# onion_dock.net
KiCad netlist of a schematic drawn in Altium Designer
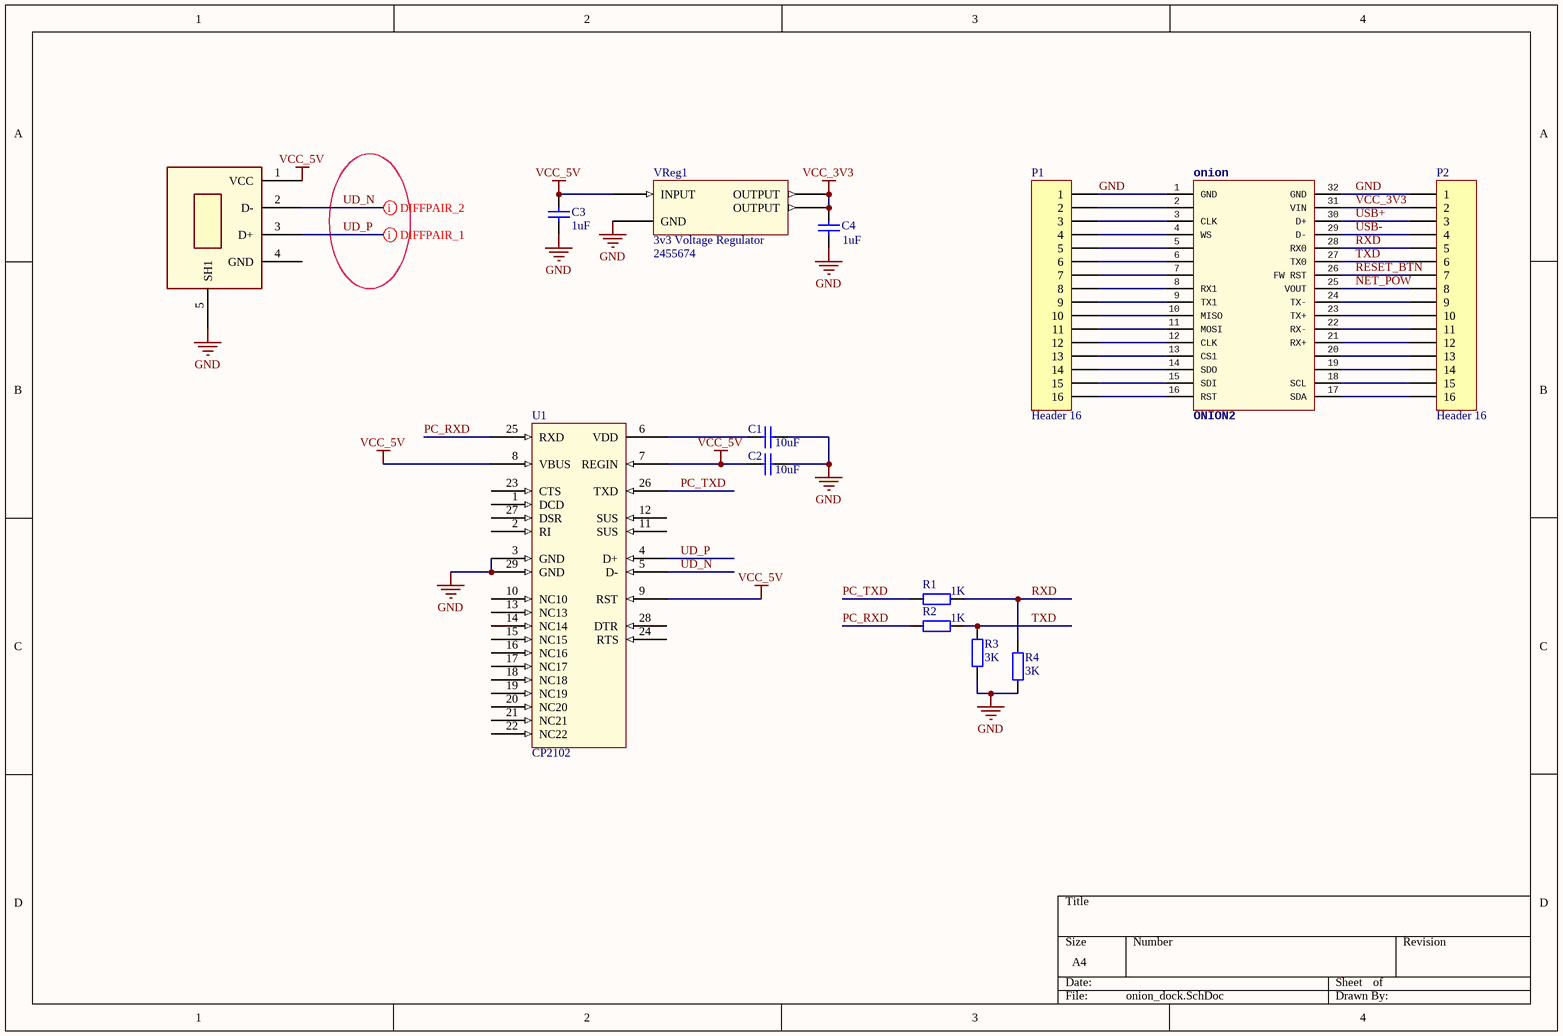
[diagram p0: onion_dock.SchDoc]

(export (version "E")
  (design (tool "Eeschema 10.0.6"))
  (components
    (comp (ref "C1")
      (value "10uF")
      (footprint "C0805")
      (description "SMD Multilayer Ceramic Capacitor, 10 µF, ± 10%, X5R, 25 V, 0805 [2012 Metric]")
      (fields (field (name "Comment") "C0805_10uF_25V"))
      (libsource (lib "Capacitors") (part "C0805_10uF_25V"))
    )
    (comp (ref "C2")
      (value "10uF")
      (footprint "C0805")
      (description "SMD Multilayer Ceramic Capacitor, 10 µF, ± 10%, X5R, 25 V, 0805 [2012 Metric]")
      (fields (field (name "Comment") "C0805_10uF_25V"))
      (libsource (lib "Capacitors") (part "C0805_10uF_25V"))
    )
    (comp (ref "C3")
      (value "1uF")
      (footprint "C0805")
      (description "SMD Multilayer Ceramic Capacitor, 1 µF, ± 10%, X7R, 25 V, 0805 [2012 Metric]")
      (fields (field (name "Comment") "C0805_1uF_25V"))
      (libsource (lib "Capacitors") (part "C0805_1uF_25V"))
    )
    (comp (ref "C4")
      (value "1uF")
      (footprint "C0805")
      (description "SMD Multilayer Ceramic Capacitor, 1 µF, ± 10%, X7R, 25 V, 0805 [2012 Metric]")
      (fields (field (name "Comment") "C0805_1uF_25V"))
      (libsource (lib "Capacitors") (part "C0805_1uF_25V"))
    )
    (comp (ref "onion") (value "ONION2") (footprint "ONION2") (libsource (lib "ICs") (part "ONION2")))
    (comp (ref "P1")
      (value "Header 16")
      (footprint "HDR1X16")
      (description "Header, 16-Pin")
      (fields (field (name "PUBLISHER") "Altium Limited"))
      (libsource (lib "Connectors") (part "Header 16"))
    )
    (comp (ref "P2")
      (value "Header 16")
      (footprint "HDR1X16")
      (description "Header, 16-Pin")
      (fields (field (name "PUBLISHER") "Altium Limited"))
      (libsource (lib "") (part "Header 16_1"))
    )
    (comp (ref "R1")
      (value "1K")
      (footprint "R0805")
      (description "RES, THICK FILM, 1K, 1%,100mW, 0805")
      (fields (field (name "POWER") "0.1W") (field (name "Comment") "R0805_1K_100mW"))
      (libsource (lib "Resistors") (part "R0805_1K_100mW"))
    )
    (comp (ref "R2")
      (value "1K")
      (footprint "R0805")
      (description "RES, THICK FILM, 1K, 1%,100mW, 0805")
      (fields (field (name "POWER") "0.1W") (field (name "Comment") "R0805_1K_100mW"))
      (libsource (lib "Resistors") (part "R0805_1K_100mW"))
    )
    (comp (ref "R3")
      (value "3K")
      (footprint "R0805")
      (description "RES, THICK FILM, 1K, 1%,100mW, 0805")
      (fields (field (name "Comment") "R0805_1K_100mW"))
      (libsource (lib "Resistors") (part "R0805_1K_100mW"))
    )
    (comp (ref "R4")
      (value "3K")
      (footprint "R0805")
      (description "RES, THICK FILM, 1K, 1%,100mW, 0805")
      (fields (field (name "Comment") "R0805_1K_100mW"))
      (libsource (lib "Resistors") (part "R0805_1K_100mW"))
    )
    (comp (ref "U1")
      (value "CP2102")
      (footprint "QFN50P500X500X100_HS-29N")
      (libsource (lib "ICs") (part "CP2102"))
    )
    (comp (ref "USB") (value "USB") (footprint "MicroUSB") (libsource (lib "Connectors") (part "USB")))
    (comp (ref "VReg1")
      (value "3v3 Voltage Regulator")
      (footprint "SOT230P700X180-4N")
      (fields (field (name "SUPPLIER PART NUMBER 1") "2455674"))
      (libsource (lib "ICs") (part "1117LV33"))
    )
  )
  (nets
    (net (code "1") (name "/NET_POW") (class "Default")
      (node (ref "P2") (pin "8") (pinfunction "8_8") (pintype "passive"))
      (node (ref "onion") (pin "25") (pinfunction "VOUT_25") (pintype "passive"))
    )
    (net (code "2") (name "/PC_RXD") (class "Default")
      (node (ref "R2") (pin "1") (pinfunction "1_1") (pintype "passive"))
      (node (ref "U1") (pin "25") (pinfunction "RXD_25") (pintype "input"))
    )
    (net (code "3") (name "/PC_TXD") (class "Default")
      (node (ref "R1") (pin "1") (pinfunction "1_1") (pintype "passive"))
      (node (ref "U1") (pin "26") (pinfunction "TXD_26") (pintype "input"))
    )
    (net (code "4") (name "/RESET_BTN") (class "Default")
      (node (ref "P2") (pin "7") (pinfunction "7_7") (pintype "passive"))
      (node (ref "onion") (pin "26") (pinfunction "FW_RST_26") (pintype "passive"))
    )
    (net (code "5") (name "/RXD") (class "Default")
      (node (ref "P2") (pin "5") (pinfunction "5_5") (pintype "passive"))
      (node (ref "R1") (pin "2") (pinfunction "2_2") (pintype "passive"))
      (node (ref "R4") (pin "2") (pinfunction "2_2") (pintype "passive"))
      (node (ref "onion") (pin "28") (pinfunction "RX0_28") (pintype "passive"))
    )
    (net (code "6") (name "/TXD") (class "Default")
      (node (ref "P2") (pin "6") (pinfunction "6_6") (pintype "passive"))
      (node (ref "R2") (pin "2") (pinfunction "2_2") (pintype "passive"))
      (node (ref "R3") (pin "2") (pinfunction "2_2") (pintype "passive"))
      (node (ref "onion") (pin "27") (pinfunction "TX0_27") (pintype "passive"))
    )
    (net (code "7") (name "/UD_N") (class "Default")
      (node (ref "U1") (pin "5") (pinfunction "D-_5") (pintype "input"))
      (node (ref "USB") (pin "2") (pinfunction "D-_2") (pintype "passive"))
    )
    (net (code "8") (name "/UD_P") (class "Default")
      (node (ref "U1") (pin "4") (pinfunction "D+_4") (pintype "input"))
      (node (ref "USB") (pin "3") (pinfunction "D+_3") (pintype "passive"))
    )
    (net (code "9") (name "/USB+") (class "Default")
      (node (ref "P2") (pin "3") (pinfunction "3_3") (pintype "passive"))
      (node (ref "onion") (pin "30") (pinfunction "D+_30") (pintype "passive"))
    )
    (net (code "10") (name "/USB-") (class "Default")
      (node (ref "P2") (pin "4") (pinfunction "4_4") (pintype "passive"))
      (node (ref "onion") (pin "29") (pinfunction "D-_29") (pintype "passive"))
    )
    (net (code "11") (name "GND") (class "Default")
      (node (ref "C1") (pin "2") (pinfunction "2_2") (pintype "passive"))
      (node (ref "C2") (pin "2") (pinfunction "2_2") (pintype "passive"))
      (node (ref "C3") (pin "1") (pinfunction "1_1") (pintype "passive"))
      (node (ref "C4") (pin "1") (pinfunction "1_1") (pintype "passive"))
      (node (ref "P1") (pin "1") (pinfunction "1_1") (pintype "passive"))
      (node (ref "P2") (pin "1") (pinfunction "1_1") (pintype "passive"))
      (node (ref "R3") (pin "1") (pinfunction "1_1") (pintype "passive"))
      (node (ref "R4") (pin "1") (pinfunction "1_1") (pintype "passive"))
      (node (ref "U1") (pin "29") (pinfunction "GND_29") (pintype "input"))
      (node (ref "U1") (pin "3") (pinfunction "GND_3") (pintype "input"))
      (node (ref "USB") (pin "5") (pinfunction "SH1_5") (pintype "passive"))
      (node (ref "VReg1") (pin "1") (pinfunction "GND_1") (pintype "power_in"))
      (node (ref "onion") (pin "1") (pinfunction "GND_1") (pintype "passive"))
      (node (ref "onion") (pin "32") (pinfunction "GND_32") (pintype "passive"))
    )
    (net (code "12") (name "Net-(P1-Pad2)") (class "Default")
      (node (ref "P1") (pin "2") (pinfunction "2_2") (pintype "passive"))
      (node (ref "onion") (pin "2") (pintype "passive"))
    )
    (net (code "13") (name "Net-(P1-Pad3)") (class "Default")
      (node (ref "P1") (pin "3") (pinfunction "3_3") (pintype "passive"))
      (node (ref "onion") (pin "3") (pinfunction "CLK_3") (pintype "passive"))
    )
    (net (code "14") (name "Net-(P1-Pad5)") (class "Default")
      (node (ref "P1") (pin "5") (pinfunction "5_5") (pintype "passive"))
      (node (ref "onion") (pin "5") (pintype "passive"))
    )
    (net (code "15") (name "Net-(P1-Pad6)") (class "Default")
      (node (ref "P1") (pin "6") (pinfunction "6_6") (pintype "passive"))
      (node (ref "onion") (pin "6") (pintype "passive"))
    )
    (net (code "16") (name "Net-(P1-Pad7)") (class "Default")
      (node (ref "P1") (pin "7") (pinfunction "7_7") (pintype "passive"))
      (node (ref "onion") (pin "7") (pintype "passive"))
    )
    (net (code "17") (name "Net-(P1-Pad12)") (class "Default")
      (node (ref "P1") (pin "12") (pinfunction "12_12") (pintype "passive"))
      (node (ref "onion") (pin "12") (pinfunction "CLK_12") (pintype "passive"))
    )
    (net (code "18") (name "Net-(P2-Pad13)") (class "Default")
      (node (ref "P2") (pin "13") (pinfunction "13_13") (pintype "passive"))
      (node (ref "onion") (pin "20") (pintype "passive"))
    )
    (net (code "19") (name "Net-(P2-Pad14)") (class "Default")
      (node (ref "P2") (pin "14") (pinfunction "14_14") (pintype "passive"))
      (node (ref "onion") (pin "19") (pintype "passive"))
    )
    (net (code "20") (name "Net-(U1-VDD)") (class "Default")
      (node (ref "C1") (pin "1") (pinfunction "1_1") (pintype "passive"))
      (node (ref "U1") (pin "6") (pinfunction "VDD_6") (pintype "open_collector"))
    )
    (net (code "21") (name "Net-(onion-CS1)") (class "Default")
      (node (ref "P1") (pin "13") (pinfunction "13_13") (pintype "passive"))
      (node (ref "onion") (pin "13") (pinfunction "CS1_13") (pintype "passive"))
    )
    (net (code "22") (name "Net-(onion-MISO)") (class "Default")
      (node (ref "P1") (pin "10") (pinfunction "10_10") (pintype "passive"))
      (node (ref "onion") (pin "10") (pinfunction "MISO_10") (pintype "passive"))
    )
    (net (code "23") (name "Net-(onion-MOSI)") (class "Default")
      (node (ref "P1") (pin "11") (pinfunction "11_11") (pintype "passive"))
      (node (ref "onion") (pin "11") (pinfunction "MOSI_11") (pintype "passive"))
    )
    (net (code "24") (name "Net-(onion-RST)") (class "Default")
      (node (ref "P1") (pin "16") (pinfunction "16_16") (pintype "passive"))
      (node (ref "onion") (pin "16") (pinfunction "RST_16") (pintype "passive"))
    )
    (net (code "25") (name "Net-(onion-RX+)") (class "Default")
      (node (ref "P2") (pin "12") (pinfunction "12_12") (pintype "passive"))
      (node (ref "onion") (pin "21") (pinfunction "RX+_21") (pintype "passive"))
    )
    (net (code "26") (name "Net-(onion-RX-)") (class "Default")
      (node (ref "P2") (pin "11") (pinfunction "11_11") (pintype "passive"))
      (node (ref "onion") (pin "22") (pinfunction "RX-_22") (pintype "passive"))
    )
    (net (code "27") (name "Net-(onion-RX1)") (class "Default")
      (node (ref "P1") (pin "8") (pinfunction "8_8") (pintype "passive"))
      (node (ref "onion") (pin "8") (pinfunction "RX1_8") (pintype "passive"))
    )
    (net (code "28") (name "Net-(onion-SCL)") (class "Default")
      (node (ref "P2") (pin "15") (pinfunction "15_15") (pintype "passive"))
      (node (ref "onion") (pin "18") (pinfunction "SCL_18") (pintype "passive"))
    )
    (net (code "29") (name "Net-(onion-SDA)") (class "Default")
      (node (ref "P2") (pin "16") (pinfunction "16_16") (pintype "passive"))
      (node (ref "onion") (pin "17") (pinfunction "SDA_17") (pintype "passive"))
    )
    (net (code "30") (name "Net-(onion-SDI)") (class "Default")
      (node (ref "P1") (pin "15") (pinfunction "15_15") (pintype "passive"))
      (node (ref "onion") (pin "15") (pinfunction "SDI_15") (pintype "passive"))
    )
    (net (code "31") (name "Net-(onion-SDO)") (class "Default")
      (node (ref "P1") (pin "14") (pinfunction "14_14") (pintype "passive"))
      (node (ref "onion") (pin "14") (pinfunction "SDO_14") (pintype "passive"))
    )
    (net (code "32") (name "Net-(onion-TX+)") (class "Default")
      (node (ref "P2") (pin "10") (pinfunction "10_10") (pintype "passive"))
      (node (ref "onion") (pin "23") (pinfunction "TX+_23") (pintype "passive"))
    )
    (net (code "33") (name "Net-(onion-TX-)") (class "Default")
      (node (ref "P2") (pin "9") (pinfunction "9_9") (pintype "passive"))
      (node (ref "onion") (pin "24") (pinfunction "TX-_24") (pintype "passive"))
    )
    (net (code "34") (name "Net-(onion-TX1)") (class "Default")
      (node (ref "P1") (pin "9") (pinfunction "9_9") (pintype "passive"))
      (node (ref "onion") (pin "9") (pinfunction "TX1_9") (pintype "passive"))
    )
    (net (code "35") (name "Net-(onion-WS)") (class "Default")
      (node (ref "P1") (pin "4") (pinfunction "4_4") (pintype "passive"))
      (node (ref "onion") (pin "4") (pinfunction "WS_4") (pintype "passive"))
    )
    (net (code "36") (name "VCC_3V3") (class "Default")
      (node (ref "C4") (pin "2") (pinfunction "2_2") (pintype "passive"))
      (node (ref "P2") (pin "2") (pinfunction "2_2") (pintype "passive"))
      (node (ref "VReg1") (pin "2") (pinfunction "OUTPUT_2") (pintype "output"))
      (node (ref "VReg1") (pin "4") (pinfunction "OUTPUT_4") (pintype "output"))
      (node (ref "onion") (pin "31") (pinfunction "VIN_31") (pintype "passive"))
    )
    (net (code "37") (name "VCC_5V") (class "Default")
      (node (ref "C2") (pin "1") (pinfunction "1_1") (pintype "passive"))
      (node (ref "C3") (pin "2") (pinfunction "2_2") (pintype "passive"))
      (node (ref "U1") (pin "7") (pinfunction "REGIN_7") (pintype "input"))
      (node (ref "U1") (pin "8") (pinfunction "VBUS_8") (pintype "input"))
      (node (ref "U1") (pin "9") (pinfunction "RST_9") (pintype "input"))
      (node (ref "USB") (pin "1") (pinfunction "VCC_1") (pintype "power_in"))
      (node (ref "VReg1") (pin "3") (pinfunction "INPUT_3") (pintype "input"))
    )
    (net (code "38") (name "unconnected-(U1-CTS-Pad23)") (class "Default")
      (node (ref "U1") (pin "23") (pinfunction "CTS_23") (pintype "input"))
    )
    (net (code "39") (name "unconnected-(U1-DCD-Pad1)") (class "Default")
      (node (ref "U1") (pin "1") (pinfunction "DCD_1") (pintype "input"))
    )
    (net (code "40") (name "unconnected-(U1-DSR-Pad27)") (class "Default")
      (node (ref "U1") (pin "27") (pinfunction "DSR_27") (pintype "input"))
    )
    (net (code "41") (name "unconnected-(U1-DTR-Pad28)") (class "Default")
      (node (ref "U1") (pin "28") (pinfunction "DTR_28") (pintype "input"))
    )
    (net (code "42") (name "unconnected-(U1-NC10-Pad10)") (class "Default")
      (node (ref "U1") (pin "10") (pinfunction "NC10_10") (pintype "input"))
    )
    (net (code "43") (name "unconnected-(U1-NC13-Pad13)") (class "Default")
      (node (ref "U1") (pin "13") (pinfunction "NC13_13") (pintype "input"))
    )
    (net (code "44") (name "unconnected-(U1-NC14-Pad14)") (class "Default")
      (node (ref "U1") (pin "14") (pinfunction "NC14_14") (pintype "input"))
    )
    (net (code "45") (name "unconnected-(U1-NC15-Pad15)") (class "Default")
      (node (ref "U1") (pin "15") (pinfunction "NC15_15") (pintype "input"))
    )
    (net (code "46") (name "unconnected-(U1-NC16-Pad16)") (class "Default")
      (node (ref "U1") (pin "16") (pinfunction "NC16_16") (pintype "input"))
    )
    (net (code "47") (name "unconnected-(U1-NC17-Pad17)") (class "Default")
      (node (ref "U1") (pin "17") (pinfunction "NC17_17") (pintype "input"))
    )
    (net (code "48") (name "unconnected-(U1-NC18-Pad18)") (class "Default")
      (node (ref "U1") (pin "18") (pinfunction "NC18_18") (pintype "input"))
    )
    (net (code "49") (name "unconnected-(U1-NC19-Pad19)") (class "Default")
      (node (ref "U1") (pin "19") (pinfunction "NC19_19") (pintype "input"))
    )
    (net (code "50") (name "unconnected-(U1-NC20-Pad20)") (class "Default")
      (node (ref "U1") (pin "20") (pinfunction "NC20_20") (pintype "input"))
    )
    (net (code "51") (name "unconnected-(U1-NC21-Pad21)") (class "Default")
      (node (ref "U1") (pin "21") (pinfunction "NC21_21") (pintype "input"))
    )
    (net (code "52") (name "unconnected-(U1-NC22-Pad22)") (class "Default")
      (node (ref "U1") (pin "22") (pinfunction "NC22_22") (pintype "input"))
    )
    (net (code "53") (name "unconnected-(U1-RI-Pad2)") (class "Default")
      (node (ref "U1") (pin "2") (pinfunction "RI_2") (pintype "input"))
    )
    (net (code "54") (name "unconnected-(U1-RTS-Pad24)") (class "Default")
      (node (ref "U1") (pin "24") (pinfunction "RTS_24") (pintype "input"))
    )
    (net (code "55") (name "unconnected-(U1-SUS-Pad11)") (class "Default")
      (node (ref "U1") (pin "11") (pinfunction "SUS_11") (pintype "input"))
    )
    (net (code "56") (name "unconnected-(U1-SUS-Pad12)") (class "Default")
      (node (ref "U1") (pin "12") (pinfunction "SUS_12") (pintype "input"))
    )
    (net (code "57") (name "unconnected-(USB-GND-Pad4)") (class "Default")
      (node (ref "USB") (pin "4") (pinfunction "GND_4") (pintype "power_in"))
    )
  )
)
